# SpaceDisplayButtonBoard_SCH.net
KiCad netlist of a schematic drawn in Altium Designer
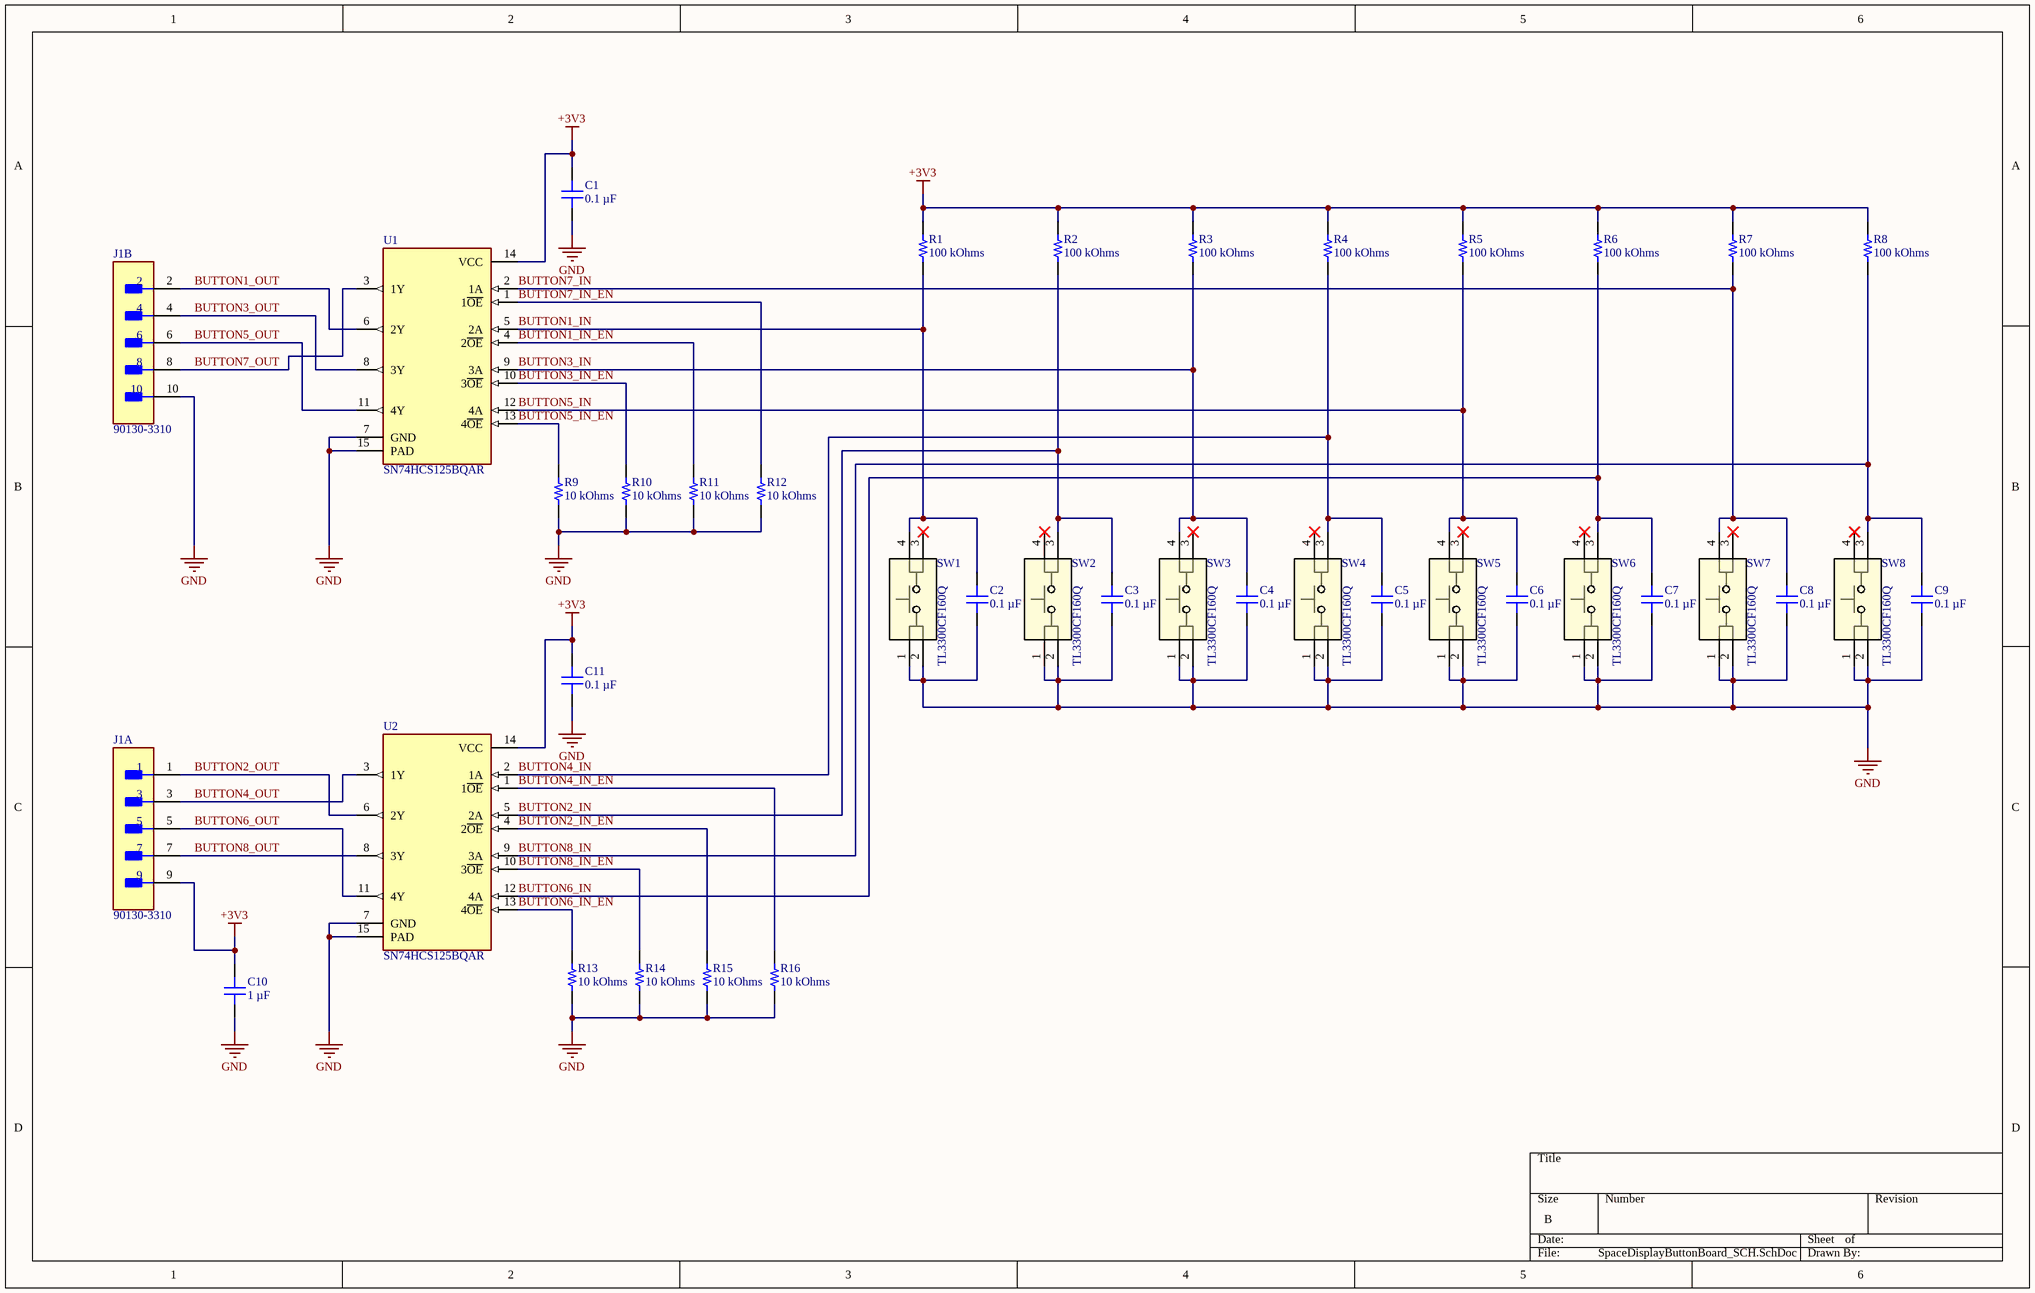
[diagram p0: SpaceDisplayButtonBoard_SCH.SchDoc]

(export (version "E")
  (design (tool "Eeschema 10.0.6"))
  (components
    (comp (ref "C1")
      (value "0.1 µF")
      (footprint "CAP 0603_1608")
      (description "CAP CER 0.1UF 25V X7R 0603")
      (fields
        (field (name "PART NUMBER") "CL10B104KA8WPNC")
        (field (name "CAPACITANCE") "0.1 µF")
        (field (name "MANUFACTURER") "Samsung Electro-Mechanics")
      )
      (libsource (lib "Celestial Altium Library - altium_library") (part "Capacitor"))
    )
    (comp (ref "C2")
      (value "0.1 µF")
      (footprint "CAP 0603_1608")
      (description "CAP CER 0.1UF 25V X7R 0603")
      (fields
        (field (name "PART NUMBER") "CL10B104KA8WPNC")
        (field (name "CAPACITANCE") "0.1 µF")
        (field (name "MANUFACTURER") "Samsung Electro-Mechanics")
      )
      (libsource (lib "Celestial Altium Library - altium_library") (part "Capacitor"))
    )
    (comp (ref "C3")
      (value "0.1 µF")
      (footprint "CAP 0603_1608")
      (description "CAP CER 0.1UF 25V X7R 0603")
      (fields
        (field (name "PART NUMBER") "CL10B104KA8WPNC")
        (field (name "CAPACITANCE") "0.1 µF")
        (field (name "MANUFACTURER") "Samsung Electro-Mechanics")
      )
      (libsource (lib "Celestial Altium Library - altium_library") (part "Capacitor"))
    )
    (comp (ref "C4")
      (value "0.1 µF")
      (footprint "CAP 0603_1608")
      (description "CAP CER 0.1UF 25V X7R 0603")
      (fields
        (field (name "PART NUMBER") "CL10B104KA8WPNC")
        (field (name "CAPACITANCE") "0.1 µF")
        (field (name "MANUFACTURER") "Samsung Electro-Mechanics")
      )
      (libsource (lib "Celestial Altium Library - altium_library") (part "Capacitor"))
    )
    (comp (ref "C5")
      (value "0.1 µF")
      (footprint "CAP 0603_1608")
      (description "CAP CER 0.1UF 25V X7R 0603")
      (fields
        (field (name "PART NUMBER") "CL10B104KA8WPNC")
        (field (name "CAPACITANCE") "0.1 µF")
        (field (name "MANUFACTURER") "Samsung Electro-Mechanics")
      )
      (libsource (lib "Celestial Altium Library - altium_library") (part "Capacitor"))
    )
    (comp (ref "C6")
      (value "0.1 µF")
      (footprint "CAP 0603_1608")
      (description "CAP CER 0.1UF 25V X7R 0603")
      (fields
        (field (name "PART NUMBER") "CL10B104KA8WPNC")
        (field (name "CAPACITANCE") "0.1 µF")
        (field (name "MANUFACTURER") "Samsung Electro-Mechanics")
      )
      (libsource (lib "Celestial Altium Library - altium_library") (part "Capacitor"))
    )
    (comp (ref "C7")
      (value "0.1 µF")
      (footprint "CAP 0603_1608")
      (description "CAP CER 0.1UF 25V X7R 0603")
      (fields
        (field (name "PART NUMBER") "CL10B104KA8WPNC")
        (field (name "CAPACITANCE") "0.1 µF")
        (field (name "MANUFACTURER") "Samsung Electro-Mechanics")
      )
      (libsource (lib "Celestial Altium Library - altium_library") (part "Capacitor"))
    )
    (comp (ref "C8")
      (value "0.1 µF")
      (footprint "CAP 0603_1608")
      (description "CAP CER 0.1UF 25V X7R 0603")
      (fields
        (field (name "PART NUMBER") "CL10B104KA8WPNC")
        (field (name "CAPACITANCE") "0.1 µF")
        (field (name "MANUFACTURER") "Samsung Electro-Mechanics")
      )
      (libsource (lib "Celestial Altium Library - altium_library") (part "Capacitor"))
    )
    (comp (ref "C9")
      (value "0.1 µF")
      (footprint "CAP 0603_1608")
      (description "CAP CER 0.1UF 25V X7R 0603")
      (fields
        (field (name "PART NUMBER") "CL10B104KA8WPNC")
        (field (name "CAPACITANCE") "0.1 µF")
        (field (name "MANUFACTURER") "Samsung Electro-Mechanics")
      )
      (libsource (lib "Celestial Altium Library - altium_library") (part "Capacitor"))
    )
    (comp (ref "C10")
      (value "1 µF")
      (footprint "CAP 0603_1608")
      (description "CAP CER 1UF 25V X5R 0603")
      (fields
        (field (name "PART NUMBER") "CL10A105KA8NNNC")
        (field (name "CAPACITANCE") "1 µF")
        (field (name "MANUFACTURER") "Samsung Electro-Mechanics")
      )
      (libsource (lib "Celestial Altium Library - altium_library") (part "Capacitor"))
    )
    (comp (ref "C11")
      (value "0.1 µF")
      (footprint "CAP 0603_1608")
      (description "CAP CER 0.1UF 25V X7R 0603")
      (fields
        (field (name "PART NUMBER") "CL10B104KA8WPNC")
        (field (name "CAPACITANCE") "0.1 µF")
        (field (name "MANUFACTURER") "Samsung Electro-Mechanics")
      )
      (libsource (lib "Celestial Altium Library - altium_library") (part "Capacitor"))
    )
    (comp (ref "J1")
      (value "90130-3310")
      (footprint "FP-90130-3310-MFG")
      (description "90130-3310 Conn Shrouded Header (4 Sides) HDR 10 POS 2.54mm Solder RA Thru-Hole C-Grid III™ Frame")
      (libsource (lib "Altium Content Vault") (part "544f42128f4185dcb88ce1ce9bf1982"))
    )
    (comp (ref "R1")
      (value "100 kOhms")
      (footprint "RES 0603_1608")
      (description "RES 100K OHM 1% 1/10W 0603")
      (fields
        (field (name "PART NUMBER") "RMCF0603FT100K")
        (field (name "MANUFACTURER") "Stackpole Electronics Inc")
      )
      (libsource (lib "Celestial Altium Library - altium_library") (part "Resistor"))
    )
    (comp (ref "R2")
      (value "100 kOhms")
      (footprint "RES 0603_1608")
      (description "RES 100K OHM 1% 1/10W 0603")
      (fields
        (field (name "PART NUMBER") "RMCF0603FT100K")
        (field (name "MANUFACTURER") "Stackpole Electronics Inc")
      )
      (libsource (lib "Celestial Altium Library - altium_library") (part "Resistor"))
    )
    (comp (ref "R3")
      (value "100 kOhms")
      (footprint "RES 0603_1608")
      (description "RES 100K OHM 1% 1/10W 0603")
      (fields
        (field (name "PART NUMBER") "RMCF0603FT100K")
        (field (name "MANUFACTURER") "Stackpole Electronics Inc")
      )
      (libsource (lib "Celestial Altium Library - altium_library") (part "Resistor"))
    )
    (comp (ref "R4")
      (value "100 kOhms")
      (footprint "RES 0603_1608")
      (description "RES 100K OHM 1% 1/10W 0603")
      (fields
        (field (name "PART NUMBER") "RMCF0603FT100K")
        (field (name "MANUFACTURER") "Stackpole Electronics Inc")
      )
      (libsource (lib "Celestial Altium Library - altium_library") (part "Resistor"))
    )
    (comp (ref "R5")
      (value "100 kOhms")
      (footprint "RES 0603_1608")
      (description "RES 100K OHM 1% 1/10W 0603")
      (fields
        (field (name "PART NUMBER") "RMCF0603FT100K")
        (field (name "MANUFACTURER") "Stackpole Electronics Inc")
      )
      (libsource (lib "Celestial Altium Library - altium_library") (part "Resistor"))
    )
    (comp (ref "R6")
      (value "100 kOhms")
      (footprint "RES 0603_1608")
      (description "RES 100K OHM 1% 1/10W 0603")
      (fields
        (field (name "PART NUMBER") "RMCF0603FT100K")
        (field (name "MANUFACTURER") "Stackpole Electronics Inc")
      )
      (libsource (lib "Celestial Altium Library - altium_library") (part "Resistor"))
    )
    (comp (ref "R7")
      (value "100 kOhms")
      (footprint "RES 0603_1608")
      (description "RES 100K OHM 1% 1/10W 0603")
      (fields
        (field (name "PART NUMBER") "RMCF0603FT100K")
        (field (name "MANUFACTURER") "Stackpole Electronics Inc")
      )
      (libsource (lib "Celestial Altium Library - altium_library") (part "Resistor"))
    )
    (comp (ref "R8")
      (value "100 kOhms")
      (footprint "RES 0603_1608")
      (description "RES 100K OHM 1% 1/10W 0603")
      (fields
        (field (name "PART NUMBER") "RMCF0603FT100K")
        (field (name "MANUFACTURER") "Stackpole Electronics Inc")
      )
      (libsource (lib "Celestial Altium Library - altium_library") (part "Resistor"))
    )
    (comp (ref "R9")
      (value "10 kOhms")
      (footprint "RES 0603_1608")
      (description "RES 10K OHM 1% 1/10W 0603")
      (fields
        (field (name "PART NUMBER") "RMCF0603FT10K0")
        (field (name "MANUFACTURER") "Stackpole Electronics Inc")
      )
      (libsource (lib "Celestial Altium Library - altium_library") (part "Resistor"))
    )
    (comp (ref "R10")
      (value "10 kOhms")
      (footprint "RES 0603_1608")
      (description "RES 10K OHM 1% 1/10W 0603")
      (fields
        (field (name "PART NUMBER") "RMCF0603FT10K0")
        (field (name "MANUFACTURER") "Stackpole Electronics Inc")
      )
      (libsource (lib "Celestial Altium Library - altium_library") (part "Resistor"))
    )
    (comp (ref "R11")
      (value "10 kOhms")
      (footprint "RES 0603_1608")
      (description "RES 10K OHM 1% 1/10W 0603")
      (fields
        (field (name "PART NUMBER") "RMCF0603FT10K0")
        (field (name "MANUFACTURER") "Stackpole Electronics Inc")
      )
      (libsource (lib "Celestial Altium Library - altium_library") (part "Resistor"))
    )
    (comp (ref "R12")
      (value "10 kOhms")
      (footprint "RES 0603_1608")
      (description "RES 10K OHM 1% 1/10W 0603")
      (fields
        (field (name "PART NUMBER") "RMCF0603FT10K0")
        (field (name "MANUFACTURER") "Stackpole Electronics Inc")
      )
      (libsource (lib "Celestial Altium Library - altium_library") (part "Resistor"))
    )
    (comp (ref "R13")
      (value "10 kOhms")
      (footprint "RES 0603_1608")
      (description "RES 10K OHM 1% 1/10W 0603")
      (fields
        (field (name "PART NUMBER") "RMCF0603FT10K0")
        (field (name "MANUFACTURER") "Stackpole Electronics Inc")
      )
      (libsource (lib "Celestial Altium Library - altium_library") (part "Resistor"))
    )
    (comp (ref "R14")
      (value "10 kOhms")
      (footprint "RES 0603_1608")
      (description "RES 10K OHM 1% 1/10W 0603")
      (fields
        (field (name "PART NUMBER") "RMCF0603FT10K0")
        (field (name "MANUFACTURER") "Stackpole Electronics Inc")
      )
      (libsource (lib "Celestial Altium Library - altium_library") (part "Resistor"))
    )
    (comp (ref "R15")
      (value "10 kOhms")
      (footprint "RES 0603_1608")
      (description "RES 10K OHM 1% 1/10W 0603")
      (fields
        (field (name "PART NUMBER") "RMCF0603FT10K0")
        (field (name "MANUFACTURER") "Stackpole Electronics Inc")
      )
      (libsource (lib "Celestial Altium Library - altium_library") (part "Resistor"))
    )
    (comp (ref "R16")
      (value "10 kOhms")
      (footprint "RES 0603_1608")
      (description "RES 10K OHM 1% 1/10W 0603")
      (fields
        (field (name "PART NUMBER") "RMCF0603FT10K0")
        (field (name "MANUFACTURER") "Stackpole Electronics Inc")
      )
      (libsource (lib "Celestial Altium Library - altium_library") (part "Resistor"))
    )
    (comp (ref "SW1")
      (value "TL3300CF160Q")
      (footprint "SW_TL3300CF160Q_EWI")
      (description "Description")
      (fields (field (name "COPYRIGHT") "Copyright (C) 2025 Ultra Librarian. All rights reserved."))
      (libsource (lib "PersonalLibrary") (part "TL3300CF160Q"))
    )
    (comp (ref "SW2")
      (value "TL3300CF160Q")
      (footprint "SW_TL3300CF160Q_EWI")
      (description "Description")
      (fields (field (name "COPYRIGHT") "Copyright (C) 2025 Ultra Librarian. All rights reserved."))
      (libsource (lib "PersonalLibrary") (part "TL3300CF160Q"))
    )
    (comp (ref "SW3")
      (value "TL3300CF160Q")
      (footprint "SW_TL3300CF160Q_EWI")
      (description "Description")
      (fields (field (name "COPYRIGHT") "Copyright (C) 2025 Ultra Librarian. All rights reserved."))
      (libsource (lib "PersonalLibrary") (part "TL3300CF160Q"))
    )
    (comp (ref "SW4")
      (value "TL3300CF160Q")
      (footprint "SW_TL3300CF160Q_EWI")
      (description "Description")
      (fields (field (name "COPYRIGHT") "Copyright (C) 2025 Ultra Librarian. All rights reserved."))
      (libsource (lib "PersonalLibrary") (part "TL3300CF160Q"))
    )
    (comp (ref "SW5")
      (value "TL3300CF160Q")
      (footprint "SW_TL3300CF160Q_EWI")
      (description "Description")
      (fields (field (name "COPYRIGHT") "Copyright (C) 2025 Ultra Librarian. All rights reserved."))
      (libsource (lib "PersonalLibrary") (part "TL3300CF160Q"))
    )
    (comp (ref "SW6")
      (value "TL3300CF160Q")
      (footprint "SW_TL3300CF160Q_EWI")
      (description "Description")
      (fields (field (name "COPYRIGHT") "Copyright (C) 2025 Ultra Librarian. All rights reserved."))
      (libsource (lib "PersonalLibrary") (part "TL3300CF160Q"))
    )
    (comp (ref "SW7")
      (value "TL3300CF160Q")
      (footprint "SW_TL3300CF160Q_EWI")
      (description "Description")
      (fields (field (name "COPYRIGHT") "Copyright (C) 2025 Ultra Librarian. All rights reserved."))
      (libsource (lib "PersonalLibrary") (part "TL3300CF160Q"))
    )
    (comp (ref "SW8")
      (value "TL3300CF160Q")
      (footprint "SW_TL3300CF160Q_EWI")
      (description "Description")
      (fields (field (name "COPYRIGHT") "Copyright (C) 2025 Ultra Librarian. All rights reserved."))
      (libsource (lib "PersonalLibrary") (part "TL3300CF160Q"))
    )
    (comp (ref "U1")
      (value "SN74HCS125BQAR")
      (footprint "FP-BQA0014A-MFG")
      (description "IC BUFFER NON-INVERT 6V 14WQFN")
      (libsource (lib "Altium Content Vault") (part "1a3dec7eba8bb7f0e504cccfeafd73e"))
    )
    (comp (ref "U2")
      (value "SN74HCS125BQAR")
      (footprint "FP-BQA0014A-MFG")
      (description "IC BUFFER NON-INVERT 6V 14WQFN")
      (libsource (lib "Altium Content Vault") (part "1a3dec7eba8bb7f0e504cccfeafd73e"))
    )
  )
  (nets
    (net (code "1") (name "+3V3") (class "Default")
      (node (ref "C1") (pin "2") (pinfunction "2_2") (pintype "passive"))
      (node (ref "C10") (pin "2") (pinfunction "2_2") (pintype "passive"))
      (node (ref "C11") (pin "2") (pinfunction "2_2") (pintype "passive"))
      (node (ref "J1") (pin "9") (pinfunction "9_9") (pintype "passive"))
      (node (ref "R1") (pin "2") (pinfunction "2_2") (pintype "passive"))
      (node (ref "R2") (pin "2") (pinfunction "2_2") (pintype "passive"))
      (node (ref "R3") (pin "2") (pinfunction "2_2") (pintype "passive"))
      (node (ref "R4") (pin "2") (pinfunction "2_2") (pintype "passive"))
      (node (ref "R5") (pin "2") (pinfunction "2_2") (pintype "passive"))
      (node (ref "R6") (pin "2") (pinfunction "2_2") (pintype "passive"))
      (node (ref "R7") (pin "2") (pinfunction "2_2") (pintype "passive"))
      (node (ref "R8") (pin "2") (pinfunction "2_2") (pintype "passive"))
      (node (ref "U1") (pin "14") (pinfunction "VCC_14") (pintype "power_in"))
      (node (ref "U2") (pin "14") (pinfunction "VCC_14") (pintype "power_in"))
    )
    (net (code "2") (name "/BUTTON1_IN") (class "Default")
      (node (ref "C2") (pin "2") (pinfunction "2_2") (pintype "passive"))
      (node (ref "R1") (pin "1") (pinfunction "1_1") (pintype "passive"))
      (node (ref "SW1") (pin "4") (pinfunction "4_4") (pintype "passive"))
      (node (ref "U1") (pin "5") (pinfunction "2A_5") (pintype "input"))
    )
    (net (code "3") (name "/BUTTON1_IN_EN") (class "Default")
      (node (ref "R11") (pin "2") (pinfunction "2_2") (pintype "passive"))
      (node (ref "U1") (pin "4") (pinfunction "2~{OE}_4") (pintype "input"))
    )
    (net (code "4") (name "/BUTTON1_OUT") (class "Default")
      (node (ref "J1") (pin "2") (pinfunction "2_2") (pintype "passive"))
      (node (ref "U1") (pin "6") (pinfunction "2Y_6") (pintype "output"))
    )
    (net (code "5") (name "/BUTTON2_IN") (class "Default")
      (node (ref "C3") (pin "2") (pinfunction "2_2") (pintype "passive"))
      (node (ref "R2") (pin "1") (pinfunction "1_1") (pintype "passive"))
      (node (ref "SW2") (pin "3") (pinfunction "3_3") (pintype "passive"))
      (node (ref "U2") (pin "5") (pinfunction "2A_5") (pintype "input"))
    )
    (net (code "6") (name "/BUTTON2_IN_EN") (class "Default")
      (node (ref "R15") (pin "2") (pinfunction "2_2") (pintype "passive"))
      (node (ref "U2") (pin "4") (pinfunction "2~{OE}_4") (pintype "input"))
    )
    (net (code "7") (name "/BUTTON2_OUT") (class "Default")
      (node (ref "J1") (pin "1") (pinfunction "1_1") (pintype "passive"))
      (node (ref "U2") (pin "6") (pinfunction "2Y_6") (pintype "output"))
    )
    (net (code "8") (name "/BUTTON3_IN") (class "Default")
      (node (ref "C4") (pin "2") (pinfunction "2_2") (pintype "passive"))
      (node (ref "R3") (pin "1") (pinfunction "1_1") (pintype "passive"))
      (node (ref "SW3") (pin "4") (pinfunction "4_4") (pintype "passive"))
      (node (ref "U1") (pin "9") (pinfunction "3A_9") (pintype "input"))
    )
    (net (code "9") (name "/BUTTON3_IN_EN") (class "Default")
      (node (ref "R10") (pin "2") (pinfunction "2_2") (pintype "passive"))
      (node (ref "U1") (pin "10") (pinfunction "3~{OE}_10") (pintype "input"))
    )
    (net (code "10") (name "/BUTTON3_OUT") (class "Default")
      (node (ref "J1") (pin "4") (pinfunction "4_4") (pintype "passive"))
      (node (ref "U1") (pin "8") (pinfunction "3Y_8") (pintype "output"))
    )
    (net (code "11") (name "/BUTTON4_IN") (class "Default")
      (node (ref "C5") (pin "2") (pinfunction "2_2") (pintype "passive"))
      (node (ref "R4") (pin "1") (pinfunction "1_1") (pintype "passive"))
      (node (ref "SW4") (pin "3") (pinfunction "3_3") (pintype "passive"))
      (node (ref "U2") (pin "2") (pinfunction "1A_2") (pintype "input"))
    )
    (net (code "12") (name "/BUTTON4_IN_EN") (class "Default")
      (node (ref "R16") (pin "2") (pinfunction "2_2") (pintype "passive"))
      (node (ref "U2") (pin "1") (pinfunction "1~{OE}_1") (pintype "input"))
    )
    (net (code "13") (name "/BUTTON4_OUT") (class "Default")
      (node (ref "J1") (pin "3") (pinfunction "3_3") (pintype "passive"))
      (node (ref "U2") (pin "3") (pinfunction "1Y_3") (pintype "output"))
    )
    (net (code "14") (name "/BUTTON5_IN") (class "Default")
      (node (ref "C6") (pin "2") (pinfunction "2_2") (pintype "passive"))
      (node (ref "R5") (pin "1") (pinfunction "1_1") (pintype "passive"))
      (node (ref "SW5") (pin "4") (pinfunction "4_4") (pintype "passive"))
      (node (ref "U1") (pin "12") (pinfunction "4A_12") (pintype "input"))
    )
    (net (code "15") (name "/BUTTON5_IN_EN") (class "Default")
      (node (ref "R9") (pin "2") (pinfunction "2_2") (pintype "passive"))
      (node (ref "U1") (pin "13") (pinfunction "4~{OE}_13") (pintype "input"))
    )
    (net (code "16") (name "/BUTTON5_OUT") (class "Default")
      (node (ref "J1") (pin "6") (pinfunction "6_6") (pintype "passive"))
      (node (ref "U1") (pin "11") (pinfunction "4Y_11") (pintype "output"))
    )
    (net (code "17") (name "/BUTTON6_IN") (class "Default")
      (node (ref "C7") (pin "2") (pinfunction "2_2") (pintype "passive"))
      (node (ref "R6") (pin "1") (pinfunction "1_1") (pintype "passive"))
      (node (ref "SW6") (pin "3") (pinfunction "3_3") (pintype "passive"))
      (node (ref "U2") (pin "12") (pinfunction "4A_12") (pintype "input"))
    )
    (net (code "18") (name "/BUTTON6_IN_EN") (class "Default")
      (node (ref "R13") (pin "2") (pinfunction "2_2") (pintype "passive"))
      (node (ref "U2") (pin "13") (pinfunction "4~{OE}_13") (pintype "input"))
    )
    (net (code "19") (name "/BUTTON6_OUT") (class "Default")
      (node (ref "J1") (pin "5") (pinfunction "5_5") (pintype "passive"))
      (node (ref "U2") (pin "11") (pinfunction "4Y_11") (pintype "output"))
    )
    (net (code "20") (name "/BUTTON7_IN") (class "Default")
      (node (ref "C8") (pin "2") (pinfunction "2_2") (pintype "passive"))
      (node (ref "R7") (pin "1") (pinfunction "1_1") (pintype "passive"))
      (node (ref "SW7") (pin "4") (pinfunction "4_4") (pintype "passive"))
      (node (ref "U1") (pin "2") (pinfunction "1A_2") (pintype "input"))
    )
    (net (code "21") (name "/BUTTON7_IN_EN") (class "Default")
      (node (ref "R12") (pin "2") (pinfunction "2_2") (pintype "passive"))
      (node (ref "U1") (pin "1") (pinfunction "1~{OE}_1") (pintype "input"))
    )
    (net (code "22") (name "/BUTTON7_OUT") (class "Default")
      (node (ref "J1") (pin "8") (pinfunction "8_8") (pintype "passive"))
      (node (ref "U1") (pin "3") (pinfunction "1Y_3") (pintype "output"))
    )
    (net (code "23") (name "/BUTTON8_IN") (class "Default")
      (node (ref "C9") (pin "2") (pinfunction "2_2") (pintype "passive"))
      (node (ref "R8") (pin "1") (pinfunction "1_1") (pintype "passive"))
      (node (ref "SW8") (pin "3") (pinfunction "3_3") (pintype "passive"))
      (node (ref "U2") (pin "9") (pinfunction "3A_9") (pintype "input"))
    )
    (net (code "24") (name "/BUTTON8_IN_EN") (class "Default")
      (node (ref "R14") (pin "2") (pinfunction "2_2") (pintype "passive"))
      (node (ref "U2") (pin "10") (pinfunction "3~{OE}_10") (pintype "input"))
    )
    (net (code "25") (name "/BUTTON8_OUT") (class "Default")
      (node (ref "J1") (pin "7") (pinfunction "7_7") (pintype "passive"))
      (node (ref "U2") (pin "8") (pinfunction "3Y_8") (pintype "output"))
    )
    (net (code "26") (name "GND") (class "Default")
      (node (ref "C1") (pin "1") (pinfunction "1_1") (pintype "passive"))
      (node (ref "C10") (pin "1") (pinfunction "1_1") (pintype "passive"))
      (node (ref "C11") (pin "1") (pinfunction "1_1") (pintype "passive"))
      (node (ref "C2") (pin "1") (pinfunction "1_1") (pintype "passive"))
      (node (ref "C3") (pin "1") (pinfunction "1_1") (pintype "passive"))
      (node (ref "C4") (pin "1") (pinfunction "1_1") (pintype "passive"))
      (node (ref "C5") (pin "1") (pinfunction "1_1") (pintype "passive"))
      (node (ref "C6") (pin "1") (pinfunction "1_1") (pintype "passive"))
      (node (ref "C7") (pin "1") (pinfunction "1_1") (pintype "passive"))
      (node (ref "C8") (pin "1") (pinfunction "1_1") (pintype "passive"))
      (node (ref "C9") (pin "1") (pinfunction "1_1") (pintype "passive"))
      (node (ref "J1") (pin "10") (pinfunction "10_10") (pintype "passive"))
      (node (ref "R10") (pin "1") (pinfunction "1_1") (pintype "passive"))
      (node (ref "R11") (pin "1") (pinfunction "1_1") (pintype "passive"))
      (node (ref "R12") (pin "1") (pinfunction "1_1") (pintype "passive"))
      (node (ref "R13") (pin "1") (pinfunction "1_1") (pintype "passive"))
      (node (ref "R14") (pin "1") (pinfunction "1_1") (pintype "passive"))
      (node (ref "R15") (pin "1") (pinfunction "1_1") (pintype "passive"))
      (node (ref "R16") (pin "1") (pinfunction "1_1") (pintype "passive"))
      (node (ref "R9") (pin "1") (pinfunction "1_1") (pintype "passive"))
      (node (ref "SW1") (pin "1") (pinfunction "1_1") (pintype "passive"))
      (node (ref "SW1") (pin "2") (pinfunction "2_2") (pintype "passive"))
      (node (ref "SW2") (pin "1") (pinfunction "1_1") (pintype "passive"))
      (node (ref "SW2") (pin "2") (pinfunction "2_2") (pintype "passive"))
      (node (ref "SW3") (pin "1") (pinfunction "1_1") (pintype "passive"))
      (node (ref "SW3") (pin "2") (pinfunction "2_2") (pintype "passive"))
      (node (ref "SW4") (pin "1") (pinfunction "1_1") (pintype "passive"))
      (node (ref "SW4") (pin "2") (pinfunction "2_2") (pintype "passive"))
      (node (ref "SW5") (pin "1") (pinfunction "1_1") (pintype "passive"))
      (node (ref "SW5") (pin "2") (pinfunction "2_2") (pintype "passive"))
      (node (ref "SW6") (pin "1") (pinfunction "1_1") (pintype "passive"))
      (node (ref "SW6") (pin "2") (pinfunction "2_2") (pintype "passive"))
      (node (ref "SW7") (pin "1") (pinfunction "1_1") (pintype "passive"))
      (node (ref "SW7") (pin "2") (pinfunction "2_2") (pintype "passive"))
      (node (ref "SW8") (pin "1") (pinfunction "1_1") (pintype "passive"))
      (node (ref "SW8") (pin "2") (pinfunction "2_2") (pintype "passive"))
      (node (ref "U1") (pin "15") (pinfunction "PAD_15") (pintype "power_in"))
      (node (ref "U1") (pin "7") (pinfunction "GND_7") (pintype "power_in"))
      (node (ref "U2") (pin "15") (pinfunction "PAD_15") (pintype "power_in"))
      (node (ref "U2") (pin "7") (pinfunction "GND_7") (pintype "power_in"))
    )
    (net (code "27") (name "unconnected-(SW1-Pad3)") (class "Default")
      (node (ref "SW1") (pin "3") (pinfunction "3_3") (pintype "passive+no_connect"))
    )
    (net (code "28") (name "unconnected-(SW2-Pad4)") (class "Default")
      (node (ref "SW2") (pin "4") (pinfunction "4_4") (pintype "passive+no_connect"))
    )
    (net (code "29") (name "unconnected-(SW3-Pad3)") (class "Default")
      (node (ref "SW3") (pin "3") (pinfunction "3_3") (pintype "passive+no_connect"))
    )
    (net (code "30") (name "unconnected-(SW4-Pad4)") (class "Default")
      (node (ref "SW4") (pin "4") (pinfunction "4_4") (pintype "passive+no_connect"))
    )
    (net (code "31") (name "unconnected-(SW5-Pad3)") (class "Default")
      (node (ref "SW5") (pin "3") (pinfunction "3_3") (pintype "passive+no_connect"))
    )
    (net (code "32") (name "unconnected-(SW6-Pad4)") (class "Default")
      (node (ref "SW6") (pin "4") (pinfunction "4_4") (pintype "passive+no_connect"))
    )
    (net (code "33") (name "unconnected-(SW7-Pad3)") (class "Default")
      (node (ref "SW7") (pin "3") (pinfunction "3_3") (pintype "passive+no_connect"))
    )
    (net (code "34") (name "unconnected-(SW8-Pad4)") (class "Default")
      (node (ref "SW8") (pin "4") (pinfunction "4_4") (pintype "passive+no_connect"))
    )
  )
)
